# touch-2ch-v2.net
KiCad netlist of a schematic drawn in Altium Designer
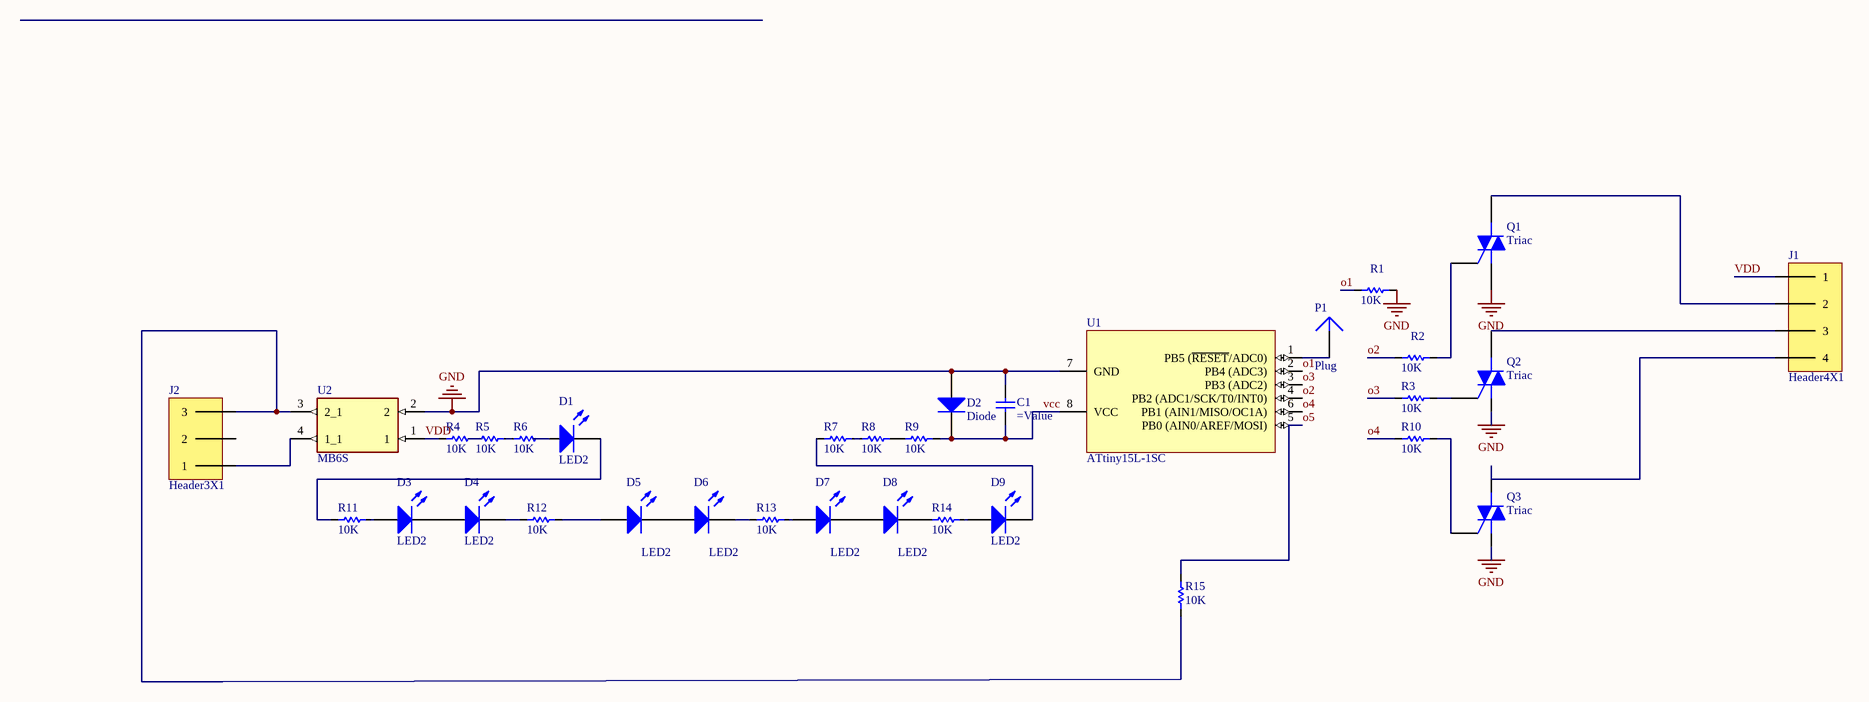
[diagram p0: touch-2ch-v2.SchDoc]

(export (version "E")
  (design (tool "Eeschema 10.0.6"))
  (components
    (comp (ref "C1")
      (value "~")
      (footprint "CAP 1206")
      (description "Capacitor")
      (libsource (lib "AltiumLib1") (part "Capacitor"))
    )
    (comp (ref "D1")
      (value "LED2")
      (footprint "3.2X1.6X1.1")
      (description "Typical RED, GREEN, YELLOW, AMBER GaAs LED")
      (fields (field (name "PUBLISHER") "Altium Limited"))
      (libsource (lib "Miscellaneous Devices") (part "LED2"))
    )
    (comp (ref "D2")
      (value "Diode")
      (footprint "C1206")
      (description "Default Diode")
      (fields (field (name "PUBLISHER") "Altium Limited"))
      (libsource (lib "Miscellaneous Devices") (part "Diode"))
    )
    (comp (ref "D3")
      (value "LED2")
      (footprint "3.2X1.6X1.1")
      (description "Typical RED, GREEN, YELLOW, AMBER GaAs LED")
      (fields (field (name "PUBLISHER") "Altium Limited"))
      (libsource (lib "Miscellaneous Devices") (part "LED2"))
    )
    (comp (ref "D4")
      (value "LED2")
      (footprint "3.2X1.6X1.1")
      (description "Typical RED, GREEN, YELLOW, AMBER GaAs LED")
      (fields (field (name "PUBLISHER") "Altium Limited"))
      (libsource (lib "Miscellaneous Devices") (part "LED2"))
    )
    (comp (ref "D5")
      (value "LED2")
      (footprint "3.2X1.6X1.1")
      (description "Typical RED, GREEN, YELLOW, AMBER GaAs LED")
      (fields (field (name "PUBLISHER") "Altium Limited"))
      (libsource (lib "Miscellaneous Devices") (part "LED2"))
    )
    (comp (ref "D6")
      (value "LED2")
      (footprint "3.2X1.6X1.1")
      (description "Typical RED, GREEN, YELLOW, AMBER GaAs LED")
      (fields (field (name "PUBLISHER") "Altium Limited"))
      (libsource (lib "Miscellaneous Devices") (part "LED2"))
    )
    (comp (ref "D7")
      (value "LED2")
      (footprint "3.2X1.6X1.1")
      (description "Typical RED, GREEN, YELLOW, AMBER GaAs LED")
      (fields (field (name "PUBLISHER") "Altium Limited"))
      (libsource (lib "Miscellaneous Devices") (part "LED2"))
    )
    (comp (ref "D8")
      (value "LED2")
      (footprint "3.2X1.6X1.1")
      (description "Typical RED, GREEN, YELLOW, AMBER GaAs LED")
      (fields (field (name "PUBLISHER") "Altium Limited"))
      (libsource (lib "Miscellaneous Devices") (part "LED2"))
    )
    (comp (ref "D9")
      (value "LED2")
      (footprint "3.2X1.6X1.1")
      (description "Typical RED, GREEN, YELLOW, AMBER GaAs LED")
      (fields (field (name "PUBLISHER") "Altium Limited"))
      (libsource (lib "Miscellaneous Devices") (part "LED2"))
    )
    (comp (ref "J1")
      (value "Header4X1")
      (footprint "HEADER 4X1")
      (libsource (lib "AltiumLib1") (part "Header4X1"))
    )
    (comp (ref "J2")
      (value "Header3X1")
      (footprint "HEADER 3X1")
      (libsource (lib "AltiumLib1") (part "Header3X1"))
    )
    (comp (ref "P1")
      (value "Plug")
      (footprint "PIN1")
      (fields (field (name "PUBLISHER") "Altium Limited"))
      (libsource (lib "Miscellaneous Connectors") (part "Plug"))
    )
    (comp (ref "Q1")
      (value "Triac")
      (footprint "SOT89N")
      (description "Silicon Bidirectional Triode Thyristor")
      (fields (field (name "PUBLISHER") "Altium Limited"))
      (libsource (lib "Miscellaneous Devices") (part "Triac"))
    )
    (comp (ref "Q2")
      (value "Triac")
      (footprint "SOT89N")
      (description "Silicon Bidirectional Triode Thyristor")
      (fields (field (name "PUBLISHER") "Altium Limited"))
      (libsource (lib "Miscellaneous Devices") (part "Triac"))
    )
    (comp (ref "Q3")
      (value "Triac")
      (footprint "SOT89N")
      (description "Silicon Bidirectional Triode Thyristor")
      (fields (field (name "PUBLISHER") "Altium Limited"))
      (libsource (lib "Miscellaneous Devices") (part "Triac"))
    )
    (comp (ref "R1")
      (value "10K")
      (footprint "RES 1206 (3216X08L)")
      (description "Resistor")
      (fields (field (name "TOLERANCE") "5%") (field (name "POWER") "1/4 W"))
      (libsource (lib "AltiumLib1") (part "Resistor"))
    )
    (comp (ref "R2")
      (value "10K")
      (footprint "RES 1206 (3216X08L)")
      (description "Resistor")
      (fields (field (name "TOLERANCE") "5%") (field (name "POWER") "1/4 W"))
      (libsource (lib "AltiumLib1") (part "Resistor"))
    )
    (comp (ref "R3")
      (value "10K")
      (footprint "RES 1206 (3216X08L)")
      (description "Resistor")
      (fields (field (name "TOLERANCE") "5%") (field (name "POWER") "1/4 W"))
      (libsource (lib "AltiumLib1") (part "Resistor"))
    )
    (comp (ref "R4")
      (value "10K")
      (footprint "RES 2010 (5026X08L)")
      (description "Resistor")
      (fields (field (name "TOLERANCE") "5%") (field (name "POWER") "1/4 W"))
      (libsource (lib "AltiumLib1") (part "Resistor"))
    )
    (comp (ref "R5")
      (value "10K")
      (footprint "RES 2010 (5026X08L)")
      (description "Resistor")
      (fields (field (name "TOLERANCE") "5%") (field (name "POWER") "1/4 W"))
      (libsource (lib "AltiumLib1") (part "Resistor"))
    )
    (comp (ref "R6")
      (value "10K")
      (footprint "RES 2010 (5026X08L)")
      (description "Resistor")
      (fields (field (name "TOLERANCE") "5%") (field (name "POWER") "1/4 W"))
      (libsource (lib "AltiumLib1") (part "Resistor"))
    )
    (comp (ref "R7")
      (value "10K")
      (footprint "RES 2010 (5026X08L)")
      (description "Resistor")
      (fields (field (name "TOLERANCE") "5%") (field (name "POWER") "1/4 W"))
      (libsource (lib "AltiumLib1") (part "Resistor"))
    )
    (comp (ref "R8")
      (value "10K")
      (footprint "RES 2010 (5026X08L)")
      (description "Resistor")
      (fields (field (name "TOLERANCE") "5%") (field (name "POWER") "1/4 W"))
      (libsource (lib "AltiumLib1") (part "Resistor"))
    )
    (comp (ref "R9")
      (value "10K")
      (footprint "RES 2010 (5026X08L)")
      (description "Resistor")
      (fields (field (name "TOLERANCE") "5%") (field (name "POWER") "1/4 W"))
      (libsource (lib "AltiumLib1") (part "Resistor"))
    )
    (comp (ref "R10")
      (value "10K")
      (footprint "RES 1206 (3216X08L)")
      (description "Resistor")
      (fields (field (name "TOLERANCE") "5%") (field (name "POWER") "1/4 W"))
      (libsource (lib "AltiumLib1") (part "Resistor"))
    )
    (comp (ref "R11")
      (value "10K")
      (footprint "RES 2010 (5026X08L)")
      (description "Resistor")
      (fields (field (name "TOLERANCE") "5%") (field (name "POWER") "1/4 W"))
      (libsource (lib "AltiumLib1") (part "Resistor"))
    )
    (comp (ref "R12")
      (value "10K")
      (footprint "RES 2010 (5026X08L)")
      (description "Resistor")
      (fields (field (name "TOLERANCE") "5%") (field (name "POWER") "1/4 W"))
      (libsource (lib "AltiumLib1") (part "Resistor"))
    )
    (comp (ref "R13")
      (value "10K")
      (footprint "RES 2010 (5026X08L)")
      (description "Resistor")
      (fields (field (name "TOLERANCE") "5%") (field (name "POWER") "1/4 W"))
      (libsource (lib "AltiumLib1") (part "Resistor"))
    )
    (comp (ref "R14")
      (value "10K")
      (footprint "RES 2010 (5026X08L)")
      (description "Resistor")
      (fields (field (name "TOLERANCE") "5%") (field (name "POWER") "1/4 W"))
      (libsource (lib "AltiumLib1") (part "Resistor"))
    )
    (comp (ref "R15")
      (value "10K")
      (footprint "RES 1206 (3216X08L)")
      (description "Resistor")
      (fields (field (name "TOLERANCE") "5%") (field (name "POWER") "1/4 W"))
      (libsource (lib "AltiumLib1") (part "Resistor"))
    )
    (comp (ref "U1")
      (value "ATtiny15L-1SC")
      (footprint "8S2_N")
      (description "8-Bit AVR Microcontroller with 1K Byte of Flash Memory")
      (fields (field (name "PUBLISHER") "Altium Limited"))
      (libsource (lib "Atmel Microcontroller 8-Bit AVR") (part "ATtiny15L-1SC"))
    )
    (comp (ref "U2")
      (value "MB6S")
      (footprint "SOIC245P670X270-4N")
      (description "Bridge Rectifier Single Phase Standard 600V Surface Mount 4-SOIC")
      (fields (field (name "MF") "ON Semiconductor") (field (name "DIGI-KEY_PART_NUMBER") "MB6SCT-ND"))
      (libsource (lib "MB6S") (part "MB6S"))
    )
  )
  (nets
    (net (code "1") (name "/VDD") (class "Default")
      (node (ref "J1") (pin "1") (pinfunction "1_1") (pintype "passive"))
      (node (ref "R4") (pin "1") (pinfunction "1_1") (pintype "passive"))
      (node (ref "U2") (pin "1") (pinfunction "1_1") (pintype "input"))
    )
    (net (code "2") (name "/o1") (class "Default")
      (node (ref "R1") (pin "1") (pinfunction "1_1") (pintype "passive"))
      (node (ref "U1") (pin "2") (pinfunction "PB4_(ADC3)_2") (pintype "bidirectional"))
    )
    (net (code "3") (name "/o2") (class "Default")
      (node (ref "R2") (pin "1") (pinfunction "1_1") (pintype "passive"))
      (node (ref "U1") (pin "4") (pinfunction "PB2_(ADC1/SCK/T0/INT0)_4") (pintype "bidirectional"))
    )
    (net (code "4") (name "/o3") (class "Default")
      (node (ref "R3") (pin "1") (pinfunction "1_1") (pintype "passive"))
      (node (ref "U1") (pin "3") (pinfunction "PB3_(ADC2)_3") (pintype "bidirectional"))
    )
    (net (code "5") (name "/o4") (class "Default")
      (node (ref "R10") (pin "1") (pinfunction "1_1") (pintype "passive"))
      (node (ref "U1") (pin "6") (pinfunction "PB1_(AIN1/MISO/OC1A)_6") (pintype "bidirectional"))
    )
    (net (code "6") (name "/o5") (class "Default")
      (node (ref "R15") (pin "2") (pinfunction "2_2") (pintype "passive"))
      (node (ref "U1") (pin "5") (pinfunction "PB0_(AIN0/AREF/MOSI)_5") (pintype "bidirectional"))
    )
    (net (code "7") (name "/vcc") (class "Default")
      (node (ref "C1") (pin "1") (pinfunction "+_1") (pintype "passive"))
      (node (ref "D2") (pin "2") (pinfunction "K_2") (pintype "passive"))
      (node (ref "R9") (pin "2") (pinfunction "2_2") (pintype "passive"))
      (node (ref "U1") (pin "8") (pinfunction "VCC_8") (pintype "power_in"))
    )
    (net (code "8") (name "GND") (class "Default")
      (node (ref "C1") (pin "2") (pinfunction "-_2") (pintype "passive"))
      (node (ref "D2") (pin "1") (pinfunction "A_1") (pintype "passive"))
      (node (ref "Q1") (pin "1") (pinfunction "M1_1") (pintype "passive"))
      (node (ref "Q2") (pin "1") (pinfunction "M1_1") (pintype "passive"))
      (node (ref "Q3") (pin "1") (pinfunction "M1_1") (pintype "passive"))
      (node (ref "R1") (pin "2") (pinfunction "2_2") (pintype "passive"))
      (node (ref "U1") (pin "7") (pinfunction "GND_7") (pintype "power_in"))
      (node (ref "U2") (pin "2") (pinfunction "2_2") (pintype "input"))
    )
    (net (code "9") (name "Net-(D1-A)") (class "Default")
      (node (ref "D1") (pin "1") (pinfunction "A_1") (pintype "passive"))
      (node (ref "R6") (pin "2") (pinfunction "2_2") (pintype "passive"))
    )
    (net (code "10") (name "Net-(D1-K)") (class "Default")
      (node (ref "D1") (pin "2") (pinfunction "K_2") (pintype "passive"))
      (node (ref "R11") (pin "1") (pinfunction "1_1") (pintype "passive"))
    )
    (net (code "11") (name "Net-(D3-A)") (class "Default")
      (node (ref "D3") (pin "1") (pinfunction "A_1") (pintype "passive"))
      (node (ref "R11") (pin "2") (pinfunction "2_2") (pintype "passive"))
    )
    (net (code "12") (name "Net-(D3-K)") (class "Default")
      (node (ref "D3") (pin "2") (pinfunction "K_2") (pintype "passive"))
      (node (ref "D4") (pin "1") (pinfunction "A_1") (pintype "passive"))
    )
    (net (code "13") (name "Net-(D4-K)") (class "Default")
      (node (ref "D4") (pin "2") (pinfunction "K_2") (pintype "passive"))
      (node (ref "R12") (pin "1") (pinfunction "1_1") (pintype "passive"))
    )
    (net (code "14") (name "Net-(D5-A)") (class "Default")
      (node (ref "D5") (pin "1") (pinfunction "A_1") (pintype "passive"))
      (node (ref "R12") (pin "2") (pinfunction "2_2") (pintype "passive"))
    )
    (net (code "15") (name "Net-(D5-K)") (class "Default")
      (node (ref "D5") (pin "2") (pinfunction "K_2") (pintype "passive"))
      (node (ref "D6") (pin "1") (pinfunction "A_1") (pintype "passive"))
    )
    (net (code "16") (name "Net-(D6-K)") (class "Default")
      (node (ref "D6") (pin "2") (pinfunction "K_2") (pintype "passive"))
      (node (ref "R13") (pin "1") (pinfunction "1_1") (pintype "passive"))
    )
    (net (code "17") (name "Net-(D7-A)") (class "Default")
      (node (ref "D7") (pin "1") (pinfunction "A_1") (pintype "passive"))
      (node (ref "R13") (pin "2") (pinfunction "2_2") (pintype "passive"))
    )
    (net (code "18") (name "Net-(D7-K)") (class "Default")
      (node (ref "D7") (pin "2") (pinfunction "K_2") (pintype "passive"))
      (node (ref "D8") (pin "1") (pinfunction "A_1") (pintype "passive"))
    )
    (net (code "19") (name "Net-(D8-K)") (class "Default")
      (node (ref "D8") (pin "2") (pinfunction "K_2") (pintype "passive"))
      (node (ref "R14") (pin "1") (pinfunction "1_1") (pintype "passive"))
    )
    (net (code "20") (name "Net-(D9-A)") (class "Default")
      (node (ref "D9") (pin "1") (pinfunction "A_1") (pintype "passive"))
      (node (ref "R14") (pin "2") (pinfunction "2_2") (pintype "passive"))
    )
    (net (code "21") (name "Net-(D9-K)") (class "Default")
      (node (ref "D9") (pin "2") (pinfunction "K_2") (pintype "passive"))
      (node (ref "R7") (pin "1") (pinfunction "1_1") (pintype "passive"))
    )
    (net (code "22") (name "Net-(Q1-G)") (class "Default")
      (node (ref "Q1") (pin "3") (pinfunction "G_3") (pintype "passive"))
      (node (ref "R2") (pin "2") (pinfunction "2_2") (pintype "passive"))
    )
    (net (code "23") (name "Net-(Q1-M2)") (class "Default")
      (node (ref "J1") (pin "2") (pinfunction "2_2") (pintype "passive"))
      (node (ref "Q1") (pin "2") (pinfunction "M2_2") (pintype "passive"))
    )
    (net (code "24") (name "Net-(Q2-G)") (class "Default")
      (node (ref "Q2") (pin "3") (pinfunction "G_3") (pintype "passive"))
      (node (ref "R3") (pin "2") (pinfunction "2_2") (pintype "passive"))
    )
    (net (code "25") (name "Net-(Q2-M2)") (class "Default")
      (node (ref "J1") (pin "3") (pinfunction "3_3") (pintype "passive"))
      (node (ref "Q2") (pin "2") (pinfunction "M2_2") (pintype "passive"))
    )
    (net (code "26") (name "Net-(Q3-G)") (class "Default")
      (node (ref "Q3") (pin "3") (pinfunction "G_3") (pintype "passive"))
      (node (ref "R10") (pin "2") (pinfunction "2_2") (pintype "passive"))
    )
    (net (code "27") (name "Net-(Q3-M2)") (class "Default")
      (node (ref "J1") (pin "4") (pinfunction "4_4") (pintype "passive"))
      (node (ref "Q3") (pin "2") (pinfunction "M2_2") (pintype "passive"))
    )
    (net (code "28") (name "Net-(R4-Pad2)") (class "Default")
      (node (ref "R4") (pin "2") (pinfunction "2_2") (pintype "passive"))
      (node (ref "R5") (pin "1") (pinfunction "1_1") (pintype "passive"))
    )
    (net (code "29") (name "Net-(R5-Pad2)") (class "Default")
      (node (ref "R5") (pin "2") (pinfunction "2_2") (pintype "passive"))
      (node (ref "R6") (pin "1") (pinfunction "1_1") (pintype "passive"))
    )
    (net (code "30") (name "Net-(R7-Pad2)") (class "Default")
      (node (ref "R7") (pin "2") (pinfunction "2_2") (pintype "passive"))
      (node (ref "R8") (pin "1") (pinfunction "1_1") (pintype "passive"))
    )
    (net (code "31") (name "Net-(R8-Pad2)") (class "Default")
      (node (ref "R8") (pin "2") (pinfunction "2_2") (pintype "passive"))
      (node (ref "R9") (pin "1") (pinfunction "1_1") (pintype "passive"))
    )
    (net (code "32") (name "Net-(U1-PB5_(~{RESET}{slash}ADC0))") (class "Default")
      (node (ref "P1") (pin "1") (pinfunction "1_1") (pintype "passive"))
      (node (ref "U1") (pin "1") (pinfunction "PB5_(~{RESET}/ADC0)_1") (pintype "bidirectional"))
    )
    (net (code "33") (name "Net-(U2-1_1)") (class "Default")
      (node (ref "J2") (pin "1") (pinfunction "1_1") (pintype "passive"))
      (node (ref "U2") (pin "4") (pinfunction "1_1_4") (pintype "output"))
    )
    (net (code "34") (name "Net-(U2-2_1)") (class "Default")
      (node (ref "J2") (pin "3") (pinfunction "3_3") (pintype "passive"))
      (node (ref "R15") (pin "1") (pinfunction "1_1") (pintype "passive"))
      (node (ref "U2") (pin "3") (pinfunction "2_1_3") (pintype "output"))
    )
    (net (code "35") (name "unconnected-(J2-Pad2)") (class "Default")
      (node (ref "J2") (pin "2") (pinfunction "2_2") (pintype "passive"))
    )
  )
)
